# sch1_-_Copy.net
KiCad netlist of a schematic drawn in EAGLE
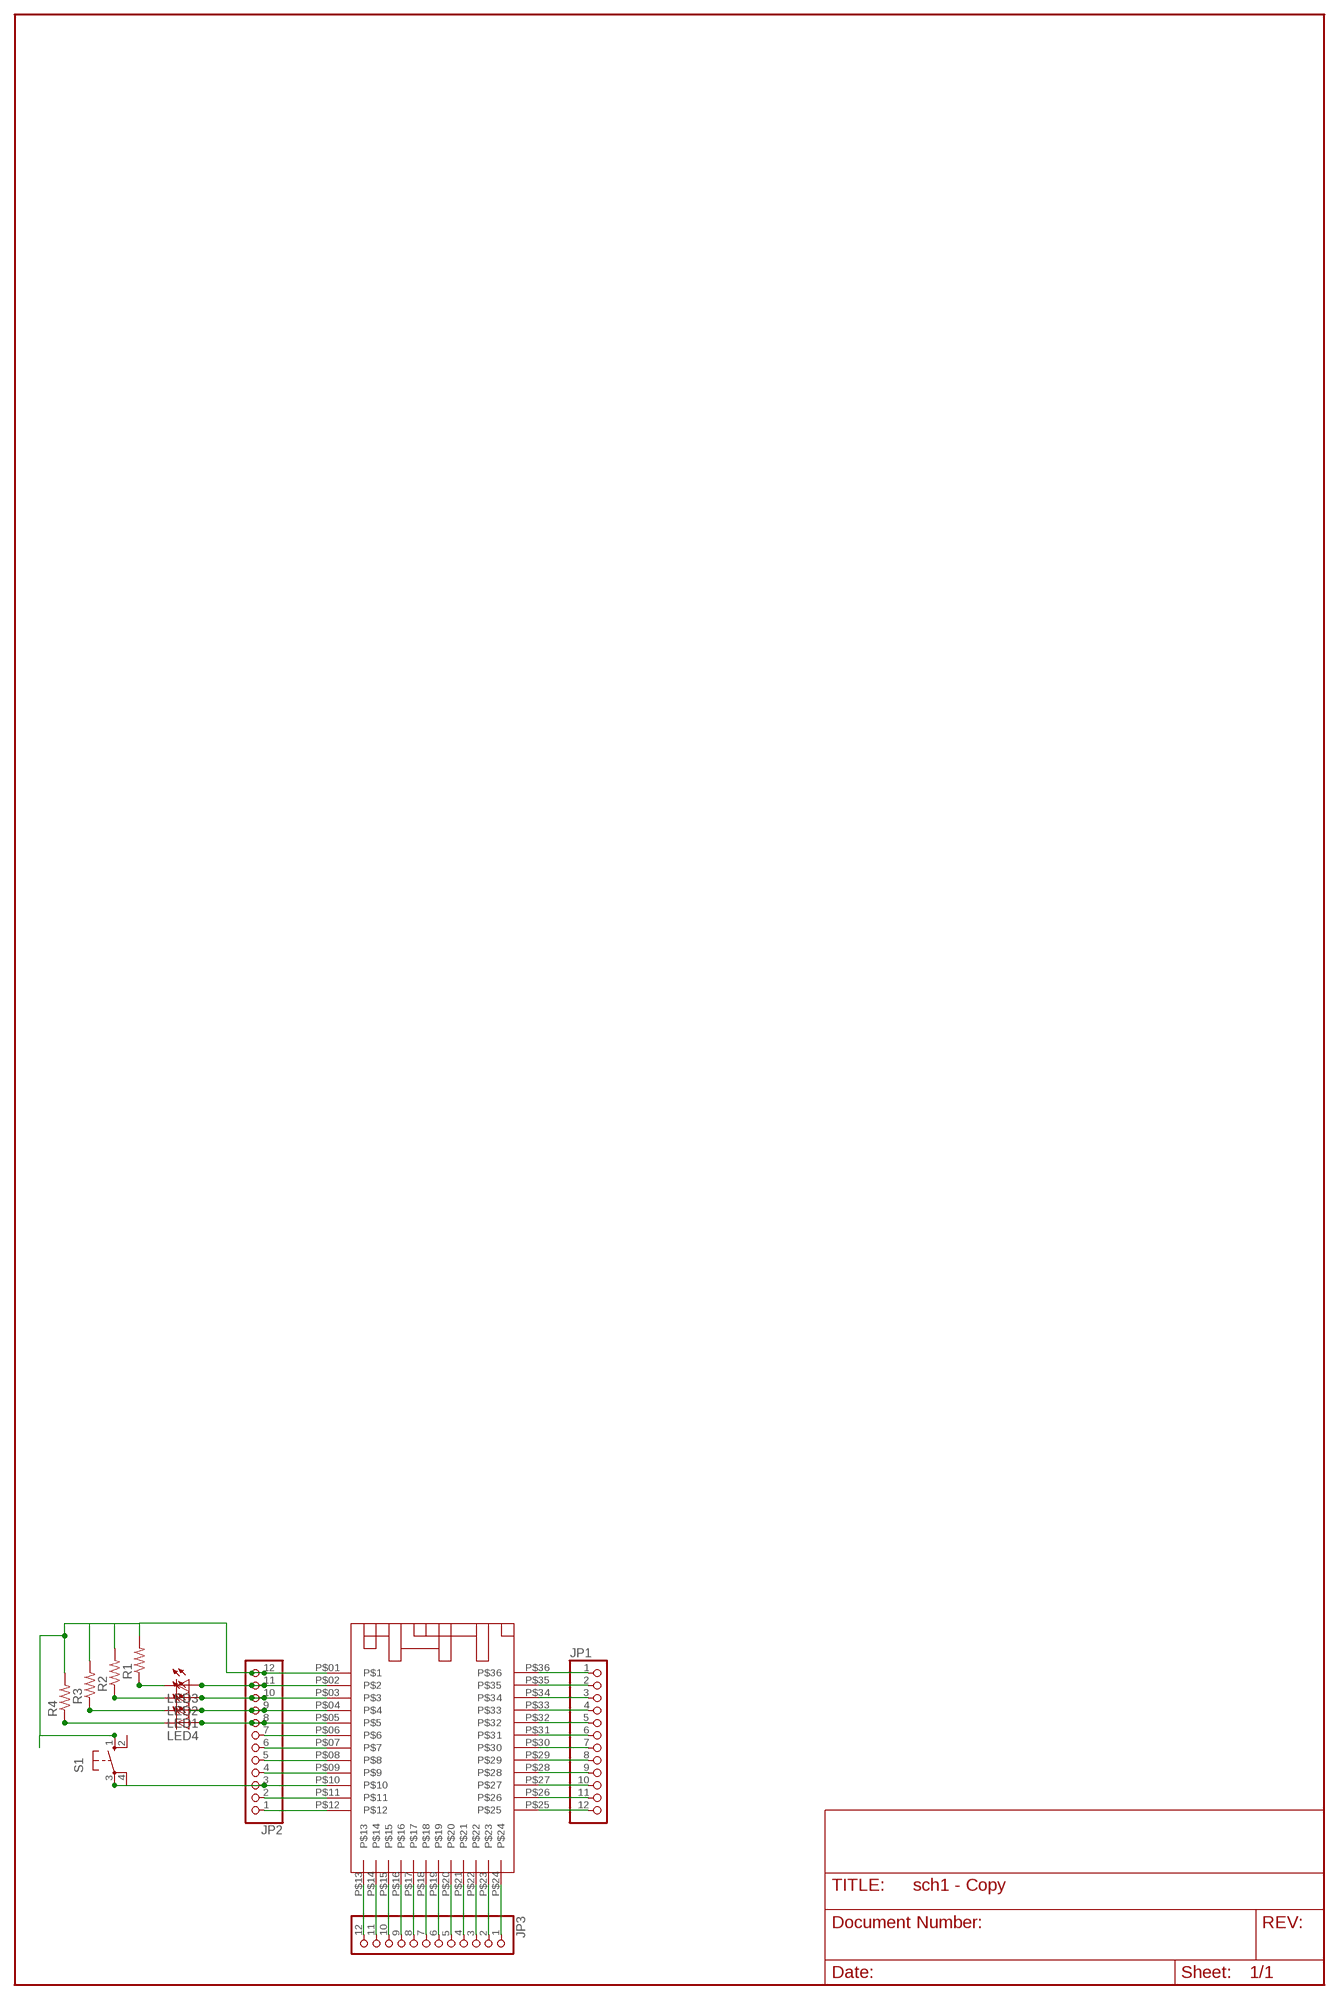
[diagram p0: schematic, sheet 1]

(export (version "E")
  (design (tool "Eeschema 10.0.6"))
  (components
    (comp (ref "JP1")
      (value "PINHD-1X12")
      (footprint "eagle-import:1X12")
      (libsource (lib "eagle-import") (part "PINHD-1X12"))
    )
    (comp (ref "JP2")
      (value "PINHD-1X12")
      (footprint "eagle-import:1X12")
      (libsource (lib "eagle-import") (part "PINHD-1X12"))
    )
    (comp (ref "JP3")
      (value "PINHD-1X12")
      (footprint "eagle-import:1X12")
      (libsource (lib "eagle-import") (part "PINHD-1X12"))
    )
    (comp (ref "LED1")
      (value "LED3MM")
      (footprint "eagle-import:LED3MM")
      (libsource (lib "eagle-import") (part "LED3MM"))
    )
    (comp (ref "LED2")
      (value "LED3MM")
      (footprint "eagle-import:LED3MM")
      (libsource (lib "eagle-import") (part "LED3MM"))
    )
    (comp (ref "LED3")
      (value "LED3MM")
      (footprint "eagle-import:LED3MM")
      (libsource (lib "eagle-import") (part "LED3MM"))
    )
    (comp (ref "LED4")
      (value "LED3MM")
      (footprint "eagle-import:LED3MM")
      (libsource (lib "eagle-import") (part "LED3MM"))
    )
    (comp (ref "R1")
      (value "R-US_0204/5")
      (footprint "eagle-import:0204_5")
      (libsource (lib "eagle-import") (part "R-US_0204/5"))
    )
    (comp (ref "R2")
      (value "R-US_0204/5")
      (footprint "eagle-import:0204_5")
      (libsource (lib "eagle-import") (part "R-US_0204/5"))
    )
    (comp (ref "R3")
      (value "R-US_0204/5")
      (footprint "eagle-import:0204_5")
      (libsource (lib "eagle-import") (part "R-US_0204/5"))
    )
    (comp (ref "R4")
      (value "R-US_0204/5")
      (footprint "eagle-import:0204_5")
      (libsource (lib "eagle-import") (part "R-US_0204/5"))
    )
    (comp (ref "S1")
      (value "10-XX")
      (footprint "eagle-import:B3F-10XX")
      (fields (field (name "MPN") "B3F-1000"))
      (libsource (lib "eagle-import") (part "10-XX"))
    )
    (comp (ref "U$1")
      (value "HZX_MODULE")
      (footprint "eagle-import:SMD_PAD_VERSION")
      (fields (field (name "AUTHOR") "Agam"))
      (libsource (lib "eagle-import") (part "HZX_MODULE"))
    )
  )
  (nets
    (net (code "1") (name "Net-(JP1-Pad1)") (class "Default")
      (node (ref "JP1") (pin "1") (pinfunction "1_1") (pintype "passive"))
      (node (ref "U$1") (pin "P$36") (pinfunction "P$36_P$36") (pintype "bidirectional"))
    )
    (net (code "2") (name "Net-(JP1-Pad2)") (class "Default")
      (node (ref "JP1") (pin "2") (pinfunction "2_2") (pintype "passive"))
      (node (ref "U$1") (pin "P$35") (pinfunction "P$35_P$35") (pintype "bidirectional"))
    )
    (net (code "3") (name "Net-(JP1-Pad3)") (class "Default")
      (node (ref "JP1") (pin "3") (pinfunction "3_3") (pintype "passive"))
      (node (ref "U$1") (pin "P$34") (pinfunction "P$34_P$34") (pintype "bidirectional"))
    )
    (net (code "4") (name "Net-(JP1-Pad4)") (class "Default")
      (node (ref "JP1") (pin "4") (pinfunction "4_4") (pintype "passive"))
      (node (ref "U$1") (pin "P$33") (pinfunction "P$33_P$33") (pintype "bidirectional"))
    )
    (net (code "5") (name "Net-(JP1-Pad5)") (class "Default")
      (node (ref "JP1") (pin "5") (pinfunction "5_5") (pintype "passive"))
      (node (ref "U$1") (pin "P$32") (pinfunction "P$32_P$32") (pintype "bidirectional"))
    )
    (net (code "6") (name "Net-(JP1-Pad6)") (class "Default")
      (node (ref "JP1") (pin "6") (pinfunction "6_6") (pintype "passive"))
      (node (ref "U$1") (pin "P$31") (pinfunction "P$31_P$31") (pintype "bidirectional"))
    )
    (net (code "7") (name "Net-(JP1-Pad7)") (class "Default")
      (node (ref "JP1") (pin "7") (pinfunction "7_7") (pintype "passive"))
      (node (ref "U$1") (pin "P$30") (pinfunction "P$30_P$30") (pintype "bidirectional"))
    )
    (net (code "8") (name "Net-(JP1-Pad8)") (class "Default")
      (node (ref "JP1") (pin "8") (pinfunction "8_8") (pintype "passive"))
      (node (ref "U$1") (pin "P$29") (pinfunction "P$29_P$29") (pintype "bidirectional"))
    )
    (net (code "9") (name "Net-(JP1-Pad9)") (class "Default")
      (node (ref "JP1") (pin "9") (pinfunction "9_9") (pintype "passive"))
      (node (ref "U$1") (pin "P$28") (pinfunction "P$28_P$28") (pintype "bidirectional"))
    )
    (net (code "10") (name "Net-(JP1-Pad10)") (class "Default")
      (node (ref "JP1") (pin "10") (pinfunction "10_10") (pintype "passive"))
      (node (ref "U$1") (pin "P$27") (pinfunction "P$27_P$27") (pintype "bidirectional"))
    )
    (net (code "11") (name "Net-(JP1-Pad11)") (class "Default")
      (node (ref "JP1") (pin "11") (pinfunction "11_11") (pintype "passive"))
      (node (ref "U$1") (pin "P$26") (pinfunction "P$26_P$26") (pintype "bidirectional"))
    )
    (net (code "12") (name "Net-(JP1-Pad12)") (class "Default")
      (node (ref "JP1") (pin "12") (pinfunction "12_12") (pintype "passive"))
      (node (ref "U$1") (pin "P$25") (pinfunction "P$25_P$25") (pintype "bidirectional"))
    )
    (net (code "13") (name "Net-(JP2-Pad1)") (class "Default")
      (node (ref "JP2") (pin "1") (pinfunction "1_1") (pintype "passive"))
      (node (ref "U$1") (pin "P$12") (pinfunction "P$12_P$12") (pintype "bidirectional"))
    )
    (net (code "14") (name "Net-(JP2-Pad2)") (class "Default")
      (node (ref "JP2") (pin "2") (pinfunction "2_2") (pintype "passive"))
      (node (ref "U$1") (pin "P$11") (pinfunction "P$11_P$11") (pintype "bidirectional"))
    )
    (net (code "15") (name "Net-(JP3-Pad1)") (class "Default")
      (node (ref "JP3") (pin "1") (pinfunction "1_1") (pintype "passive"))
      (node (ref "U$1") (pin "P$24") (pinfunction "P$24_P$24") (pintype "bidirectional"))
    )
    (net (code "16") (name "Net-(JP3-Pad2)") (class "Default")
      (node (ref "JP3") (pin "2") (pinfunction "2_2") (pintype "passive"))
      (node (ref "U$1") (pin "P$23") (pinfunction "P$23_P$23") (pintype "bidirectional"))
    )
    (net (code "17") (name "Net-(JP3-Pad3)") (class "Default")
      (node (ref "JP3") (pin "3") (pinfunction "3_3") (pintype "passive"))
      (node (ref "U$1") (pin "P$22") (pinfunction "P$22_P$22") (pintype "bidirectional"))
    )
    (net (code "18") (name "Net-(JP3-Pad4)") (class "Default")
      (node (ref "JP3") (pin "4") (pinfunction "4_4") (pintype "passive"))
      (node (ref "U$1") (pin "P$21") (pinfunction "P$21_P$21") (pintype "bidirectional"))
    )
    (net (code "19") (name "Net-(JP3-Pad5)") (class "Default")
      (node (ref "JP3") (pin "5") (pinfunction "5_5") (pintype "passive"))
      (node (ref "U$1") (pin "P$20") (pinfunction "P$20_P$20") (pintype "bidirectional"))
    )
    (net (code "20") (name "Net-(JP3-Pad6)") (class "Default")
      (node (ref "JP3") (pin "6") (pinfunction "6_6") (pintype "passive"))
      (node (ref "U$1") (pin "P$19") (pinfunction "P$19_P$19") (pintype "bidirectional"))
    )
    (net (code "21") (name "Net-(JP3-Pad7)") (class "Default")
      (node (ref "JP3") (pin "7") (pinfunction "7_7") (pintype "passive"))
      (node (ref "U$1") (pin "P$18") (pinfunction "P$18_P$18") (pintype "bidirectional"))
    )
    (net (code "22") (name "Net-(JP3-Pad8)") (class "Default")
      (node (ref "JP3") (pin "8") (pinfunction "8_8") (pintype "passive"))
      (node (ref "U$1") (pin "P$17") (pinfunction "P$17_P$17") (pintype "bidirectional"))
    )
    (net (code "23") (name "Net-(JP3-Pad9)") (class "Default")
      (node (ref "JP3") (pin "9") (pinfunction "9_9") (pintype "passive"))
      (node (ref "U$1") (pin "P$16") (pinfunction "P$16_P$16") (pintype "bidirectional"))
    )
    (net (code "24") (name "Net-(JP3-Pad10)") (class "Default")
      (node (ref "JP3") (pin "10") (pinfunction "10_10") (pintype "passive"))
      (node (ref "U$1") (pin "P$15") (pinfunction "P$15_P$15") (pintype "bidirectional"))
    )
    (net (code "25") (name "Net-(JP3-Pad11)") (class "Default")
      (node (ref "JP3") (pin "11") (pinfunction "11_11") (pintype "passive"))
      (node (ref "U$1") (pin "P$14") (pinfunction "P$14_P$14") (pintype "bidirectional"))
    )
    (net (code "26") (name "Net-(JP3-Pad12)") (class "Default")
      (node (ref "JP3") (pin "12") (pinfunction "12_12") (pintype "passive"))
      (node (ref "U$1") (pin "P$13") (pinfunction "P$13_P$13") (pintype "bidirectional"))
    )
    (net (code "27") (name "Net-(LED1-C)") (class "Default")
      (node (ref "LED1") (pin "K") (pinfunction "C_K") (pintype "passive"))
      (node (ref "R3") (pin "1") (pinfunction "1_1") (pintype "passive"))
    )
    (net (code "28") (name "Net-(LED2-C)") (class "Default")
      (node (ref "LED2") (pin "K") (pinfunction "C_K") (pintype "passive"))
      (node (ref "R2") (pin "1") (pinfunction "1_1") (pintype "passive"))
    )
    (net (code "29") (name "Net-(LED3-C)") (class "Default")
      (node (ref "LED3") (pin "K") (pinfunction "C_K") (pintype "passive"))
      (node (ref "R1") (pin "1") (pinfunction "1_1") (pintype "passive"))
    )
    (net (code "30") (name "Net-(LED4-C)") (class "Default")
      (node (ref "LED4") (pin "K") (pinfunction "C_K") (pintype "passive"))
      (node (ref "R4") (pin "1") (pinfunction "1_1") (pintype "passive"))
    )
    (net (code "31") (name "Net-(S1-P)") (class "Default")
      (node (ref "JP2") (pin "3") (pinfunction "3_3") (pintype "passive"))
      (node (ref "S1") (pin "3") (pinfunction "P_3") (pintype "passive"))
      (node (ref "U$1") (pin "P$10") (pinfunction "P$10_P$10") (pintype "bidirectional"))
    )
    (net (code "32") (name "Net-(S1-S)") (class "Default")
      (node (ref "JP2") (pin "12") (pinfunction "12_12") (pintype "passive"))
      (node (ref "R1") (pin "2") (pinfunction "2_2") (pintype "passive"))
      (node (ref "R2") (pin "2") (pinfunction "2_2") (pintype "passive"))
      (node (ref "R3") (pin "2") (pinfunction "2_2") (pintype "passive"))
      (node (ref "R4") (pin "2") (pinfunction "2_2") (pintype "passive"))
      (node (ref "S1") (pin "1") (pinfunction "S_1") (pintype "passive"))
      (node (ref "U$1") (pin "P$01") (pinfunction "P$1_P$01") (pintype "bidirectional"))
    )
    (net (code "33") (name "Net-(U$1-P$2)") (class "Default")
      (node (ref "JP2") (pin "11") (pinfunction "11_11") (pintype "passive"))
      (node (ref "LED3") (pin "A") (pinfunction "A_A") (pintype "passive"))
      (node (ref "U$1") (pin "P$02") (pinfunction "P$2_P$02") (pintype "bidirectional"))
    )
    (net (code "34") (name "Net-(U$1-P$3)") (class "Default")
      (node (ref "JP2") (pin "10") (pinfunction "10_10") (pintype "passive"))
      (node (ref "LED2") (pin "A") (pinfunction "A_A") (pintype "passive"))
      (node (ref "U$1") (pin "P$03") (pinfunction "P$3_P$03") (pintype "bidirectional"))
    )
    (net (code "35") (name "Net-(U$1-P$4)") (class "Default")
      (node (ref "JP2") (pin "9") (pinfunction "9_9") (pintype "passive"))
      (node (ref "LED1") (pin "A") (pinfunction "A_A") (pintype "passive"))
      (node (ref "U$1") (pin "P$04") (pinfunction "P$4_P$04") (pintype "bidirectional"))
    )
    (net (code "36") (name "Net-(U$1-P$5)") (class "Default")
      (node (ref "JP2") (pin "8") (pinfunction "8_8") (pintype "passive"))
      (node (ref "LED4") (pin "A") (pinfunction "A_A") (pintype "passive"))
      (node (ref "U$1") (pin "P$05") (pinfunction "P$5_P$05") (pintype "bidirectional"))
    )
    (net (code "37") (name "Net-(U$1-P$6)") (class "Default")
      (node (ref "JP2") (pin "7") (pinfunction "7_7") (pintype "passive"))
      (node (ref "U$1") (pin "P$06") (pinfunction "P$6_P$06") (pintype "bidirectional"))
    )
    (net (code "38") (name "Net-(U$1-P$7)") (class "Default")
      (node (ref "JP2") (pin "6") (pinfunction "6_6") (pintype "passive"))
      (node (ref "U$1") (pin "P$07") (pinfunction "P$7_P$07") (pintype "bidirectional"))
    )
    (net (code "39") (name "Net-(U$1-P$8)") (class "Default")
      (node (ref "JP2") (pin "5") (pinfunction "5_5") (pintype "passive"))
      (node (ref "U$1") (pin "P$08") (pinfunction "P$8_P$08") (pintype "bidirectional"))
    )
    (net (code "40") (name "Net-(U$1-P$9)") (class "Default")
      (node (ref "JP2") (pin "4") (pinfunction "4_4") (pintype "passive"))
      (node (ref "U$1") (pin "P$09") (pinfunction "P$9_P$09") (pintype "bidirectional"))
    )
    (net (code "41") (name "unconnected-(S1-P1-Pad4)") (class "Default")
      (node (ref "S1") (pin "4") (pinfunction "P1_4") (pintype "passive"))
    )
    (net (code "42") (name "unconnected-(S1-S1-Pad2)") (class "Default")
      (node (ref "S1") (pin "2") (pinfunction "S1_2") (pintype "passive"))
    )
  )
)
